# Addr.net
KiCad netlist of a schematic drawn in EAGLE
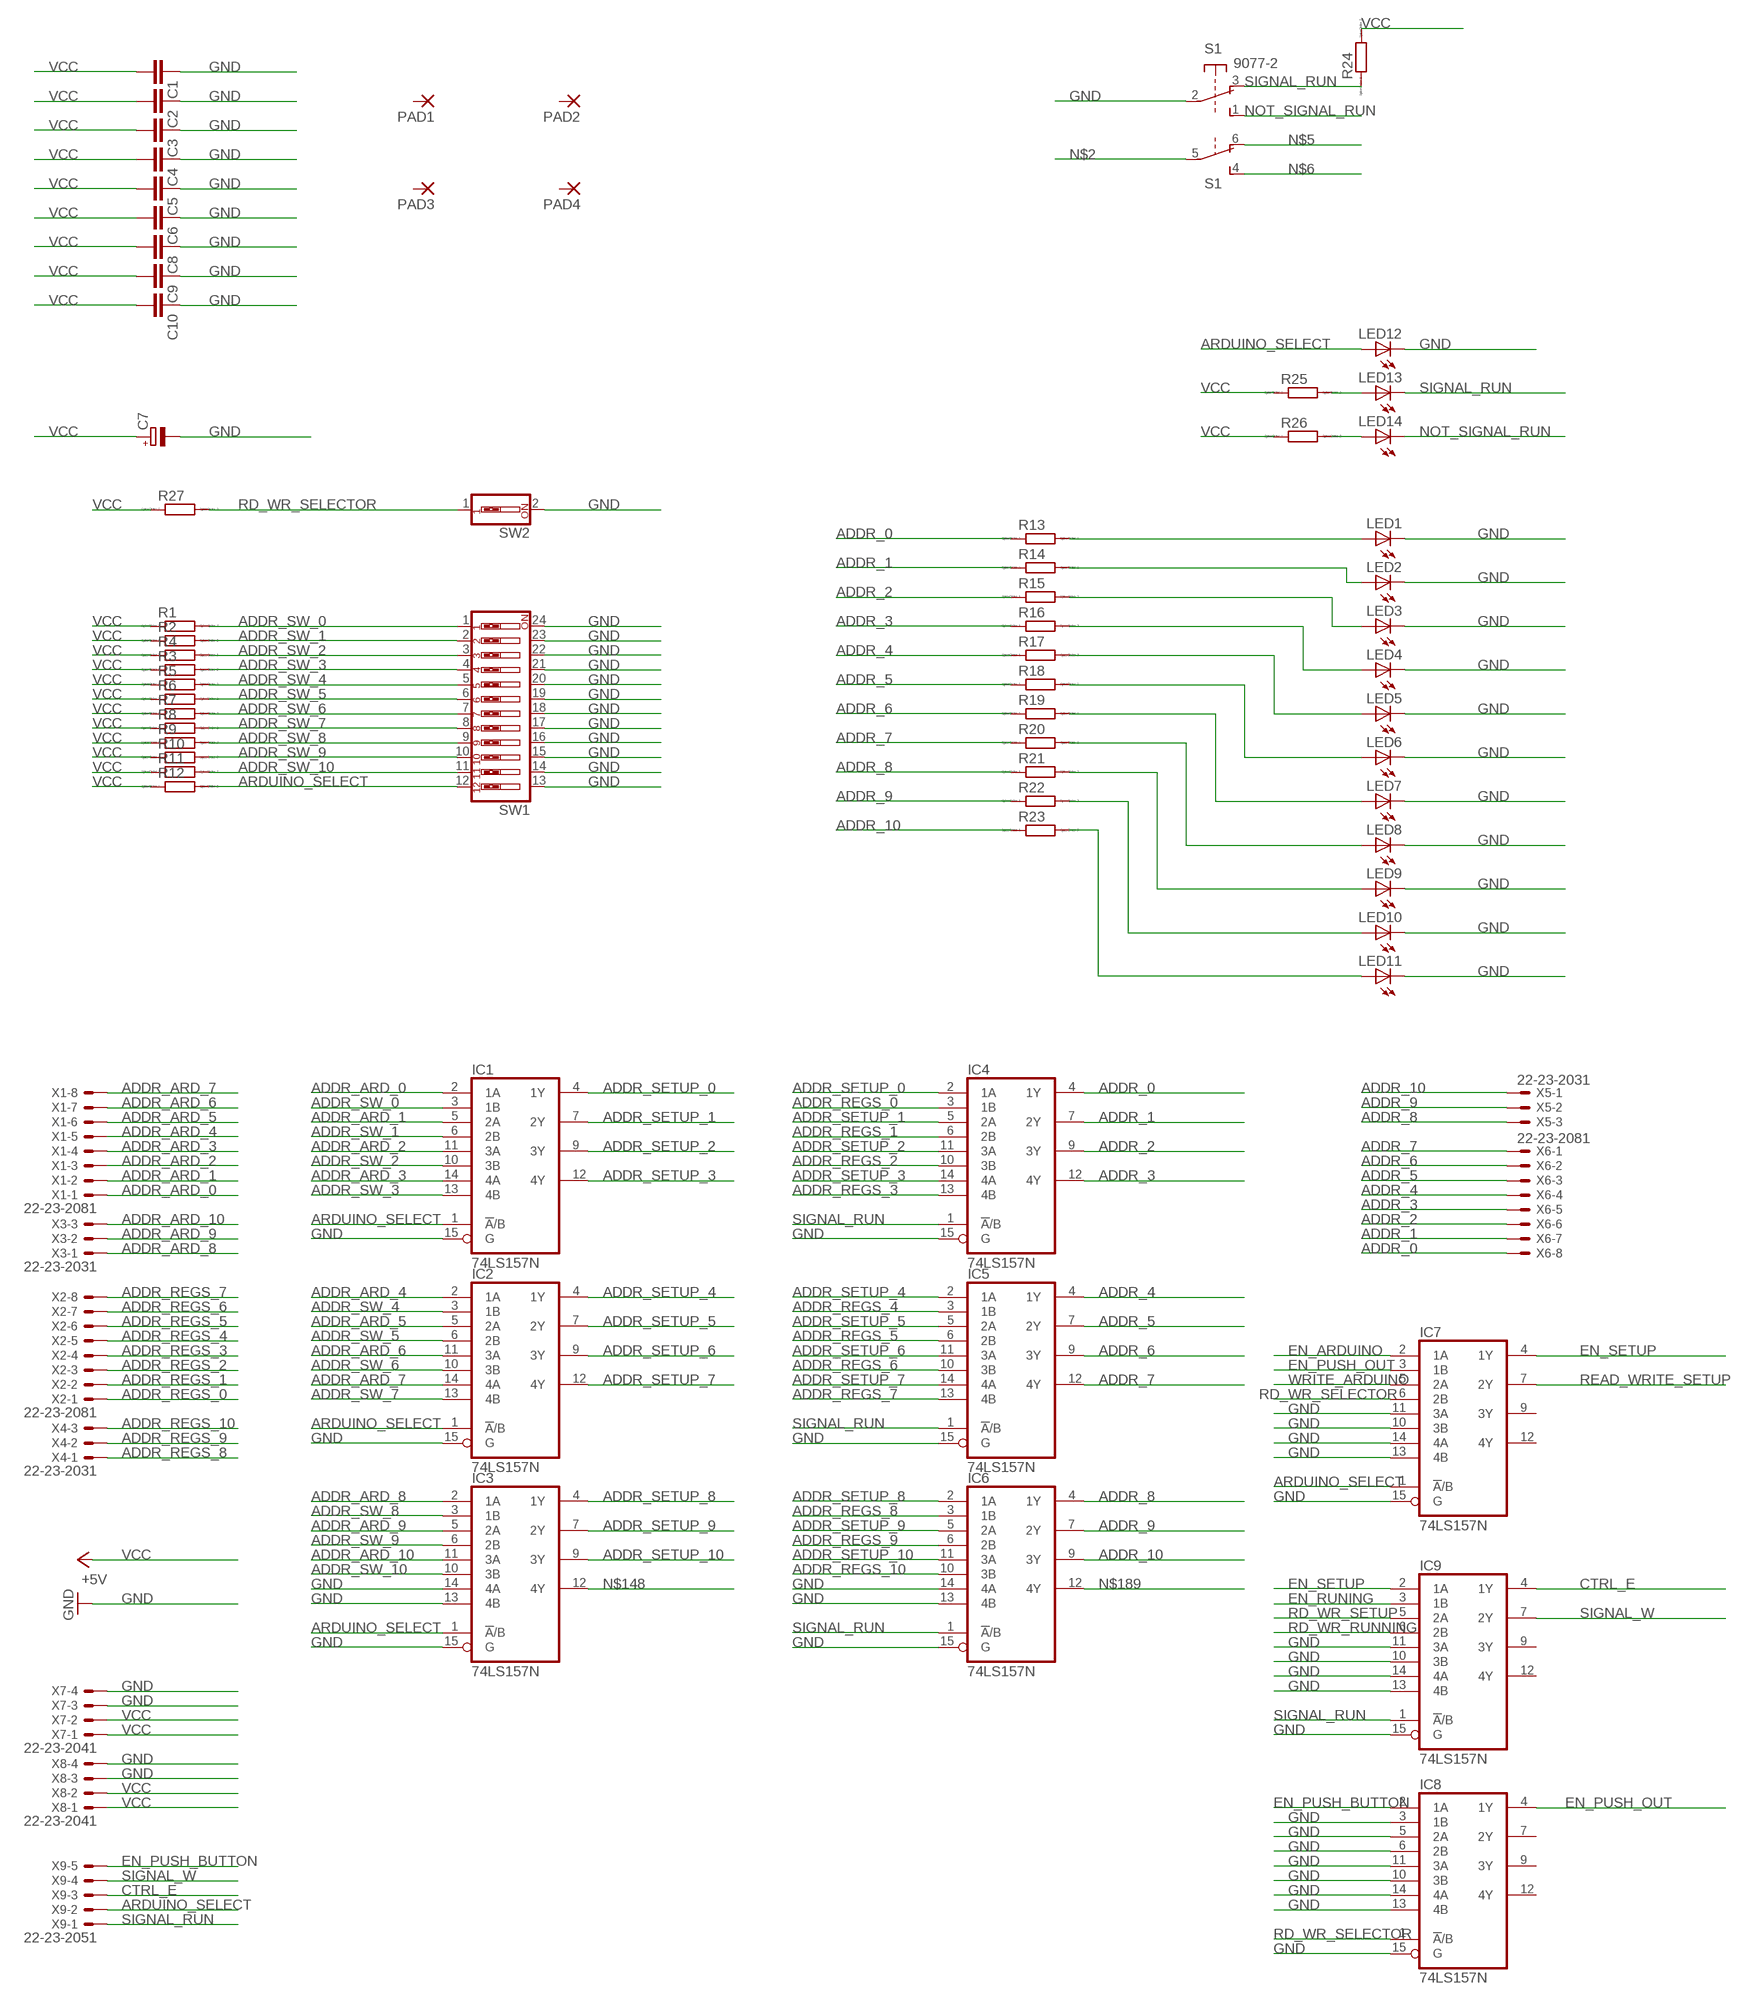
[diagram p0: schematic, sheet 1]

(export (version "E")
  (design (tool "Eeschema 10.0.6"))
  (components
    (comp (ref "C1")
      (value "C-EU025-025X050")
      (footprint "eagle-import:C025-025X050")
      (libsource (lib "eagle-import") (part "C-EU025-025X050"))
    )
    (comp (ref "C2")
      (value "C-EU025-025X050")
      (footprint "eagle-import:C025-025X050")
      (libsource (lib "eagle-import") (part "C-EU025-025X050"))
    )
    (comp (ref "C3")
      (value "C-EU025-025X050")
      (footprint "eagle-import:C025-025X050")
      (libsource (lib "eagle-import") (part "C-EU025-025X050"))
    )
    (comp (ref "C4")
      (value "C-EU025-025X050")
      (footprint "eagle-import:C025-025X050")
      (libsource (lib "eagle-import") (part "C-EU025-025X050"))
    )
    (comp (ref "C5")
      (value "C-EU025-025X050")
      (footprint "eagle-import:C025-025X050")
      (libsource (lib "eagle-import") (part "C-EU025-025X050"))
    )
    (comp (ref "C6")
      (value "C-EU025-025X050")
      (footprint "eagle-import:C025-025X050")
      (libsource (lib "eagle-import") (part "C-EU025-025X050"))
    )
    (comp (ref "C7")
      (value "CPOL-EUE2.5-6")
      (footprint "eagle-import:E2,5-6")
      (libsource (lib "eagle-import") (part "CPOL-EUE2.5-6"))
    )
    (comp (ref "C8")
      (value "C-EU025-025X050")
      (footprint "eagle-import:C025-025X050")
      (libsource (lib "eagle-import") (part "C-EU025-025X050"))
    )
    (comp (ref "C9")
      (value "C-EU025-025X050")
      (footprint "eagle-import:C025-025X050")
      (libsource (lib "eagle-import") (part "C-EU025-025X050"))
    )
    (comp (ref "C10")
      (value "C-EU025-025X050")
      (footprint "eagle-import:C025-025X050")
      (libsource (lib "eagle-import") (part "C-EU025-025X050"))
    )
    (comp (ref "IC1")
      (value "74LS157N")
      (footprint "eagle-import:DIL16")
      (libsource (lib "eagle-import") (part "74157NLS"))
    )
    (comp (ref "IC2")
      (value "74LS157N")
      (footprint "eagle-import:DIL16")
      (libsource (lib "eagle-import") (part "74157NLS"))
    )
    (comp (ref "IC3")
      (value "74LS157N")
      (footprint "eagle-import:DIL16")
      (libsource (lib "eagle-import") (part "74157NLS"))
    )
    (comp (ref "IC4")
      (value "74LS157N")
      (footprint "eagle-import:DIL16")
      (libsource (lib "eagle-import") (part "74157NLS"))
    )
    (comp (ref "IC5")
      (value "74LS157N")
      (footprint "eagle-import:DIL16")
      (libsource (lib "eagle-import") (part "74157NLS"))
    )
    (comp (ref "IC6")
      (value "74LS157N")
      (footprint "eagle-import:DIL16")
      (libsource (lib "eagle-import") (part "74157NLS"))
    )
    (comp (ref "IC7")
      (value "74LS157N")
      (footprint "eagle-import:DIL16")
      (libsource (lib "eagle-import") (part "74157NLS"))
    )
    (comp (ref "IC8")
      (value "74LS157N")
      (footprint "eagle-import:DIL16")
      (libsource (lib "eagle-import") (part "74157NLS"))
    )
    (comp (ref "IC9")
      (value "74LS157N")
      (footprint "eagle-import:DIL16")
      (libsource (lib "eagle-import") (part "74157NLS"))
    )
    (comp (ref "LED1")
      (value "LED5MM")
      (footprint "eagle-import:LED5MM")
      (libsource (lib "eagle-import") (part "LED5MM"))
    )
    (comp (ref "LED2")
      (value "LED5MM")
      (footprint "eagle-import:LED5MM")
      (libsource (lib "eagle-import") (part "LED5MM"))
    )
    (comp (ref "LED3")
      (value "LED5MM")
      (footprint "eagle-import:LED5MM")
      (libsource (lib "eagle-import") (part "LED5MM"))
    )
    (comp (ref "LED4")
      (value "LED5MM")
      (footprint "eagle-import:LED5MM")
      (libsource (lib "eagle-import") (part "LED5MM"))
    )
    (comp (ref "LED5")
      (value "LED5MM")
      (footprint "eagle-import:LED5MM")
      (libsource (lib "eagle-import") (part "LED5MM"))
    )
    (comp (ref "LED6")
      (value "LED5MM")
      (footprint "eagle-import:LED5MM")
      (libsource (lib "eagle-import") (part "LED5MM"))
    )
    (comp (ref "LED7")
      (value "LED5MM")
      (footprint "eagle-import:LED5MM")
      (libsource (lib "eagle-import") (part "LED5MM"))
    )
    (comp (ref "LED8")
      (value "LED5MM")
      (footprint "eagle-import:LED5MM")
      (libsource (lib "eagle-import") (part "LED5MM"))
    )
    (comp (ref "LED9")
      (value "LED5MM")
      (footprint "eagle-import:LED5MM")
      (libsource (lib "eagle-import") (part "LED5MM"))
    )
    (comp (ref "LED10")
      (value "LED5MM")
      (footprint "eagle-import:LED5MM")
      (libsource (lib "eagle-import") (part "LED5MM"))
    )
    (comp (ref "LED11")
      (value "LED5MM")
      (footprint "eagle-import:LED5MM")
      (libsource (lib "eagle-import") (part "LED5MM"))
    )
    (comp (ref "LED12")
      (value "LED5MM")
      (footprint "eagle-import:LED5MM")
      (libsource (lib "eagle-import") (part "LED5MM"))
    )
    (comp (ref "LED13")
      (value "LED5MM")
      (footprint "eagle-import:LED5MM")
      (libsource (lib "eagle-import") (part "LED5MM"))
    )
    (comp (ref "LED14")
      (value "LED5MM")
      (footprint "eagle-import:LED5MM")
      (libsource (lib "eagle-import") (part "LED5MM"))
    )
    (comp (ref "PAD1")
      (value "3,17/1,3")
      (footprint "eagle-import:3,17_1,3")
      (libsource (lib "eagle-import") (part "3,17/1,3"))
    )
    (comp (ref "PAD2")
      (value "3,17/1,3")
      (footprint "eagle-import:3,17_1,3")
      (libsource (lib "eagle-import") (part "3,17/1,3"))
    )
    (comp (ref "PAD3")
      (value "3,17/1,3")
      (footprint "eagle-import:3,17_1,3")
      (libsource (lib "eagle-import") (part "3,17/1,3"))
    )
    (comp (ref "PAD4")
      (value "3,17/1,3")
      (footprint "eagle-import:3,17_1,3")
      (libsource (lib "eagle-import") (part "3,17/1,3"))
    )
    (comp (ref "R1")
      (value "R0207/10")
      (footprint "eagle-import:0207_10")
      (libsource (lib "eagle-import") (part "R0207/10"))
    )
    (comp (ref "R2")
      (value "R0207/10")
      (footprint "eagle-import:0207_10")
      (libsource (lib "eagle-import") (part "R0207/10"))
    )
    (comp (ref "R3")
      (value "R0207/10")
      (footprint "eagle-import:0207_10")
      (libsource (lib "eagle-import") (part "R0207/10"))
    )
    (comp (ref "R4")
      (value "R0207/10")
      (footprint "eagle-import:0207_10")
      (libsource (lib "eagle-import") (part "R0207/10"))
    )
    (comp (ref "R5")
      (value "R0207/10")
      (footprint "eagle-import:0207_10")
      (libsource (lib "eagle-import") (part "R0207/10"))
    )
    (comp (ref "R6")
      (value "R0207/10")
      (footprint "eagle-import:0207_10")
      (libsource (lib "eagle-import") (part "R0207/10"))
    )
    (comp (ref "R7")
      (value "R0207/10")
      (footprint "eagle-import:0207_10")
      (libsource (lib "eagle-import") (part "R0207/10"))
    )
    (comp (ref "R8")
      (value "R0207/10")
      (footprint "eagle-import:0207_10")
      (libsource (lib "eagle-import") (part "R0207/10"))
    )
    (comp (ref "R9")
      (value "R0207/10")
      (footprint "eagle-import:0207_10")
      (libsource (lib "eagle-import") (part "R0207/10"))
    )
    (comp (ref "R10")
      (value "R0207/10")
      (footprint "eagle-import:0207_10")
      (libsource (lib "eagle-import") (part "R0207/10"))
    )
    (comp (ref "R11")
      (value "R0207/10")
      (footprint "eagle-import:0207_10")
      (libsource (lib "eagle-import") (part "R0207/10"))
    )
    (comp (ref "R12")
      (value "R0207/10")
      (footprint "eagle-import:0207_10")
      (libsource (lib "eagle-import") (part "R0207/10"))
    )
    (comp (ref "R13")
      (value "R0207/10")
      (footprint "eagle-import:0207_10")
      (libsource (lib "eagle-import") (part "R0207/10"))
    )
    (comp (ref "R14")
      (value "R0207/10")
      (footprint "eagle-import:0207_10")
      (libsource (lib "eagle-import") (part "R0207/10"))
    )
    (comp (ref "R15")
      (value "R0207/10")
      (footprint "eagle-import:0207_10")
      (libsource (lib "eagle-import") (part "R0207/10"))
    )
    (comp (ref "R16")
      (value "R0207/10")
      (footprint "eagle-import:0207_10")
      (libsource (lib "eagle-import") (part "R0207/10"))
    )
    (comp (ref "R17")
      (value "R0207/10")
      (footprint "eagle-import:0207_10")
      (libsource (lib "eagle-import") (part "R0207/10"))
    )
    (comp (ref "R18")
      (value "R0207/10")
      (footprint "eagle-import:0207_10")
      (libsource (lib "eagle-import") (part "R0207/10"))
    )
    (comp (ref "R19")
      (value "R0207/10")
      (footprint "eagle-import:0207_10")
      (libsource (lib "eagle-import") (part "R0207/10"))
    )
    (comp (ref "R20")
      (value "R0207/10")
      (footprint "eagle-import:0207_10")
      (libsource (lib "eagle-import") (part "R0207/10"))
    )
    (comp (ref "R21")
      (value "R0207/10")
      (footprint "eagle-import:0207_10")
      (libsource (lib "eagle-import") (part "R0207/10"))
    )
    (comp (ref "R22")
      (value "R0207/10")
      (footprint "eagle-import:0207_10")
      (libsource (lib "eagle-import") (part "R0207/10"))
    )
    (comp (ref "R23")
      (value "R0207/10")
      (footprint "eagle-import:0207_10")
      (libsource (lib "eagle-import") (part "R0207/10"))
    )
    (comp (ref "R24")
      (value "R0207/10")
      (footprint "eagle-import:0207_10")
      (libsource (lib "eagle-import") (part "R0207/10"))
    )
    (comp (ref "R25")
      (value "R0207/10")
      (footprint "eagle-import:0207_10")
      (libsource (lib "eagle-import") (part "R0207/10"))
    )
    (comp (ref "R26")
      (value "R0207/10")
      (footprint "eagle-import:0207_10")
      (libsource (lib "eagle-import") (part "R0207/10"))
    )
    (comp (ref "R27")
      (value "R0207/10")
      (footprint "eagle-import:0207_10")
      (libsource (lib "eagle-import") (part "R0207/10"))
    )
    (comp (ref "S1")
      (value "9077-2")
      (footprint "eagle-import:9077-2")
      (libsource (lib "eagle-import") (part "9077-2"))
    )
    (comp (ref "SW1")
      (value "SW_DIP-12")
      (footprint "eagle-import:EDG-12")
      (libsource (lib "eagle-import") (part "SW_DIP-12"))
    )
    (comp (ref "SW2")
      (value "SW_DIP-1")
      (footprint "eagle-import:EDG-01")
      (libsource (lib "eagle-import") (part "SW_DIP-1"))
    )
    (comp (ref "X1")
      (value "22-23-2081")
      (footprint "eagle-import:22-23-2081")
      (fields (field (name "MF") "MOLEX"))
      (libsource (lib "eagle-import") (part "22-23-2081"))
    )
    (comp (ref "X2")
      (value "22-23-2081")
      (footprint "eagle-import:22-23-2081")
      (fields (field (name "MF") "MOLEX"))
      (libsource (lib "eagle-import") (part "22-23-2081"))
    )
    (comp (ref "X3")
      (value "22-23-2031")
      (footprint "eagle-import:22-23-2031")
      (fields (field (name "MF") "MOLEX"))
      (libsource (lib "eagle-import") (part "22-23-2031"))
    )
    (comp (ref "X4")
      (value "22-23-2031")
      (footprint "eagle-import:22-23-2031")
      (fields (field (name "MF") "MOLEX"))
      (libsource (lib "eagle-import") (part "22-23-2031"))
    )
    (comp (ref "X5")
      (value "22-23-2031")
      (footprint "eagle-import:22-23-2031")
      (fields (field (name "MF") "MOLEX"))
      (libsource (lib "eagle-import") (part "22-23-2031"))
    )
    (comp (ref "X6")
      (value "22-23-2081")
      (footprint "eagle-import:22-23-2081")
      (fields (field (name "MF") "MOLEX"))
      (libsource (lib "eagle-import") (part "22-23-2081"))
    )
    (comp (ref "X7")
      (value "22-23-2041")
      (footprint "eagle-import:22-23-2041")
      (fields (field (name "MF") "MOLEX"))
      (libsource (lib "eagle-import") (part "22-23-2041"))
    )
    (comp (ref "X8")
      (value "22-23-2041")
      (footprint "eagle-import:22-23-2041")
      (fields (field (name "MF") "MOLEX"))
      (libsource (lib "eagle-import") (part "22-23-2041"))
    )
    (comp (ref "X9")
      (value "22-23-2051")
      (footprint "eagle-import:22-23-2051")
      (fields (field (name "MF") "MOLEX"))
      (libsource (lib "eagle-import") (part "22-23-2051"))
    )
  )
  (nets
    (net (code "1") (name "+5V") (class "Default")
      (node (ref "C1") (pin "2") (pinfunction "2_2") (pintype "passive"))
      (node (ref "C10") (pin "2") (pinfunction "2_2") (pintype "passive"))
      (node (ref "C2") (pin "2") (pinfunction "2_2") (pintype "passive"))
      (node (ref "C3") (pin "2") (pinfunction "2_2") (pintype "passive"))
      (node (ref "C4") (pin "2") (pinfunction "2_2") (pintype "passive"))
      (node (ref "C5") (pin "2") (pinfunction "2_2") (pintype "passive"))
      (node (ref "C6") (pin "2") (pinfunction "2_2") (pintype "passive"))
      (node (ref "C7") (pin "+") (pinfunction "+_+") (pintype "passive"))
      (node (ref "C8") (pin "2") (pinfunction "2_2") (pintype "passive"))
      (node (ref "C9") (pin "2") (pinfunction "2_2") (pintype "passive"))
      (node (ref "R1") (pin "1") (pinfunction "1_1") (pintype "passive"))
      (node (ref "R10") (pin "1") (pinfunction "1_1") (pintype "passive"))
      (node (ref "R11") (pin "1") (pinfunction "1_1") (pintype "passive"))
      (node (ref "R12") (pin "1") (pinfunction "1_1") (pintype "passive"))
      (node (ref "R2") (pin "1") (pinfunction "1_1") (pintype "passive"))
      (node (ref "R24") (pin "2") (pinfunction "2_2") (pintype "passive"))
      (node (ref "R25") (pin "1") (pinfunction "1_1") (pintype "passive"))
      (node (ref "R26") (pin "1") (pinfunction "1_1") (pintype "passive"))
      (node (ref "R27") (pin "1") (pinfunction "1_1") (pintype "passive"))
      (node (ref "R3") (pin "1") (pinfunction "1_1") (pintype "passive"))
      (node (ref "R4") (pin "1") (pinfunction "1_1") (pintype "passive"))
      (node (ref "R5") (pin "1") (pinfunction "1_1") (pintype "passive"))
      (node (ref "R6") (pin "1") (pinfunction "1_1") (pintype "passive"))
      (node (ref "R7") (pin "1") (pinfunction "1_1") (pintype "passive"))
      (node (ref "R8") (pin "1") (pinfunction "1_1") (pintype "passive"))
      (node (ref "R9") (pin "1") (pinfunction "1_1") (pintype "passive"))
      (node (ref "X7") (pin "1") (pinfunction "S_1") (pintype "passive"))
      (node (ref "X7") (pin "2") (pinfunction "S_2") (pintype "passive"))
      (node (ref "X8") (pin "1") (pinfunction "S_1") (pintype "passive"))
      (node (ref "X8") (pin "2") (pinfunction "S_2") (pintype "passive"))
    )
    (net (code "2") (name "/ADDR_0") (class "Default")
      (node (ref "IC4") (pin "4") (pinfunction "1Y_4") (pintype "output"))
      (node (ref "R13") (pin "1") (pinfunction "1_1") (pintype "passive"))
      (node (ref "X6") (pin "8") (pinfunction "S_8") (pintype "passive"))
    )
    (net (code "3") (name "/ADDR_1") (class "Default")
      (node (ref "IC4") (pin "7") (pinfunction "2Y_7") (pintype "output"))
      (node (ref "R14") (pin "1") (pinfunction "1_1") (pintype "passive"))
      (node (ref "X6") (pin "7") (pinfunction "S_7") (pintype "passive"))
    )
    (net (code "4") (name "/ADDR_2") (class "Default")
      (node (ref "IC4") (pin "9") (pinfunction "3Y_9") (pintype "output"))
      (node (ref "R15") (pin "1") (pinfunction "1_1") (pintype "passive"))
      (node (ref "X6") (pin "6") (pinfunction "S_6") (pintype "passive"))
    )
    (net (code "5") (name "/ADDR_3") (class "Default")
      (node (ref "IC4") (pin "12") (pinfunction "4Y_12") (pintype "output"))
      (node (ref "R16") (pin "1") (pinfunction "1_1") (pintype "passive"))
      (node (ref "X6") (pin "5") (pinfunction "S_5") (pintype "passive"))
    )
    (net (code "6") (name "/ADDR_4") (class "Default")
      (node (ref "IC5") (pin "4") (pinfunction "1Y_4") (pintype "output"))
      (node (ref "R17") (pin "1") (pinfunction "1_1") (pintype "passive"))
      (node (ref "X6") (pin "4") (pinfunction "S_4") (pintype "passive"))
    )
    (net (code "7") (name "/ADDR_5") (class "Default")
      (node (ref "IC5") (pin "7") (pinfunction "2Y_7") (pintype "output"))
      (node (ref "R18") (pin "1") (pinfunction "1_1") (pintype "passive"))
      (node (ref "X6") (pin "3") (pinfunction "S_3") (pintype "passive"))
    )
    (net (code "8") (name "/ADDR_6") (class "Default")
      (node (ref "IC5") (pin "9") (pinfunction "3Y_9") (pintype "output"))
      (node (ref "R19") (pin "1") (pinfunction "1_1") (pintype "passive"))
      (node (ref "X6") (pin "2") (pinfunction "S_2") (pintype "passive"))
    )
    (net (code "9") (name "/ADDR_7") (class "Default")
      (node (ref "IC5") (pin "12") (pinfunction "4Y_12") (pintype "output"))
      (node (ref "R20") (pin "1") (pinfunction "1_1") (pintype "passive"))
      (node (ref "X6") (pin "1") (pinfunction "S_1") (pintype "passive"))
    )
    (net (code "10") (name "/ADDR_8") (class "Default")
      (node (ref "IC6") (pin "4") (pinfunction "1Y_4") (pintype "output"))
      (node (ref "R21") (pin "1") (pinfunction "1_1") (pintype "passive"))
      (node (ref "X5") (pin "3") (pinfunction "S_3") (pintype "passive"))
    )
    (net (code "11") (name "/ADDR_9") (class "Default")
      (node (ref "IC6") (pin "7") (pinfunction "2Y_7") (pintype "output"))
      (node (ref "R22") (pin "1") (pinfunction "1_1") (pintype "passive"))
      (node (ref "X5") (pin "2") (pinfunction "S_2") (pintype "passive"))
    )
    (net (code "12") (name "/ADDR_10") (class "Default")
      (node (ref "IC6") (pin "9") (pinfunction "3Y_9") (pintype "output"))
      (node (ref "R23") (pin "1") (pinfunction "1_1") (pintype "passive"))
      (node (ref "X5") (pin "1") (pinfunction "S_1") (pintype "passive"))
    )
    (net (code "13") (name "/ADDR_ARD_0") (class "Default")
      (node (ref "IC1") (pin "2") (pinfunction "1A_2") (pintype "input"))
      (node (ref "X1") (pin "1") (pinfunction "S_1") (pintype "passive"))
    )
    (net (code "14") (name "/ADDR_ARD_1") (class "Default")
      (node (ref "IC1") (pin "5") (pinfunction "2A_5") (pintype "input"))
      (node (ref "X1") (pin "2") (pinfunction "S_2") (pintype "passive"))
    )
    (net (code "15") (name "/ADDR_ARD_2") (class "Default")
      (node (ref "IC1") (pin "11") (pinfunction "3A_11") (pintype "input"))
      (node (ref "X1") (pin "3") (pinfunction "S_3") (pintype "passive"))
    )
    (net (code "16") (name "/ADDR_ARD_3") (class "Default")
      (node (ref "IC1") (pin "14") (pinfunction "4A_14") (pintype "input"))
      (node (ref "X1") (pin "4") (pinfunction "S_4") (pintype "passive"))
    )
    (net (code "17") (name "/ADDR_ARD_4") (class "Default")
      (node (ref "IC2") (pin "2") (pinfunction "1A_2") (pintype "input"))
      (node (ref "X1") (pin "5") (pinfunction "S_5") (pintype "passive"))
    )
    (net (code "18") (name "/ADDR_ARD_5") (class "Default")
      (node (ref "IC2") (pin "5") (pinfunction "2A_5") (pintype "input"))
      (node (ref "X1") (pin "6") (pinfunction "S_6") (pintype "passive"))
    )
    (net (code "19") (name "/ADDR_ARD_6") (class "Default")
      (node (ref "IC2") (pin "11") (pinfunction "3A_11") (pintype "input"))
      (node (ref "X1") (pin "7") (pinfunction "S_7") (pintype "passive"))
    )
    (net (code "20") (name "/ADDR_ARD_7") (class "Default")
      (node (ref "IC2") (pin "14") (pinfunction "4A_14") (pintype "input"))
      (node (ref "X1") (pin "8") (pinfunction "S_8") (pintype "passive"))
    )
    (net (code "21") (name "/ADDR_ARD_8") (class "Default")
      (node (ref "IC3") (pin "2") (pinfunction "1A_2") (pintype "input"))
      (node (ref "X3") (pin "1") (pinfunction "S_1") (pintype "passive"))
    )
    (net (code "22") (name "/ADDR_ARD_9") (class "Default")
      (node (ref "IC3") (pin "5") (pinfunction "2A_5") (pintype "input"))
      (node (ref "X3") (pin "2") (pinfunction "S_2") (pintype "passive"))
    )
    (net (code "23") (name "/ADDR_ARD_10") (class "Default")
      (node (ref "IC3") (pin "11") (pinfunction "3A_11") (pintype "input"))
      (node (ref "X3") (pin "3") (pinfunction "S_3") (pintype "passive"))
    )
    (net (code "24") (name "/ADDR_REGS_0") (class "Default")
      (node (ref "IC4") (pin "3") (pinfunction "1B_3") (pintype "input"))
      (node (ref "X2") (pin "1") (pinfunction "S_1") (pintype "passive"))
    )
    (net (code "25") (name "/ADDR_REGS_1") (class "Default")
      (node (ref "IC4") (pin "6") (pinfunction "2B_6") (pintype "input"))
      (node (ref "X2") (pin "2") (pinfunction "S_2") (pintype "passive"))
    )
    (net (code "26") (name "/ADDR_REGS_2") (class "Default")
      (node (ref "IC4") (pin "10") (pinfunction "3B_10") (pintype "input"))
      (node (ref "X2") (pin "3") (pinfunction "S_3") (pintype "passive"))
    )
    (net (code "27") (name "/ADDR_REGS_3") (class "Default")
      (node (ref "IC4") (pin "13") (pinfunction "4B_13") (pintype "input"))
      (node (ref "X2") (pin "4") (pinfunction "S_4") (pintype "passive"))
    )
    (net (code "28") (name "/ADDR_REGS_4") (class "Default")
      (node (ref "IC5") (pin "3") (pinfunction "1B_3") (pintype "input"))
      (node (ref "X2") (pin "5") (pinfunction "S_5") (pintype "passive"))
    )
    (net (code "29") (name "/ADDR_REGS_5") (class "Default")
      (node (ref "IC5") (pin "6") (pinfunction "2B_6") (pintype "input"))
      (node (ref "X2") (pin "6") (pinfunction "S_6") (pintype "passive"))
    )
    (net (code "30") (name "/ADDR_REGS_6") (class "Default")
      (node (ref "IC5") (pin "10") (pinfunction "3B_10") (pintype "input"))
      (node (ref "X2") (pin "7") (pinfunction "S_7") (pintype "passive"))
    )
    (net (code "31") (name "/ADDR_REGS_7") (class "Default")
      (node (ref "IC5") (pin "13") (pinfunction "4B_13") (pintype "input"))
      (node (ref "X2") (pin "8") (pinfunction "S_8") (pintype "passive"))
    )
    (net (code "32") (name "/ADDR_REGS_8") (class "Default")
      (node (ref "IC6") (pin "3") (pinfunction "1B_3") (pintype "input"))
      (node (ref "X4") (pin "1") (pinfunction "S_1") (pintype "passive"))
    )
    (net (code "33") (name "/ADDR_REGS_9") (class "Default")
      (node (ref "IC6") (pin "6") (pinfunction "2B_6") (pintype "input"))
      (node (ref "X4") (pin "2") (pinfunction "S_2") (pintype "passive"))
    )
    (net (code "34") (name "/ADDR_REGS_10") (class "Default")
      (node (ref "IC6") (pin "10") (pinfunction "3B_10") (pintype "input"))
      (node (ref "X4") (pin "3") (pinfunction "S_3") (pintype "passive"))
    )
    (net (code "35") (name "/ADDR_SETUP_0") (class "Default")
      (node (ref "IC1") (pin "4") (pinfunction "1Y_4") (pintype "output"))
      (node (ref "IC4") (pin "2") (pinfunction "1A_2") (pintype "input"))
    )
    (net (code "36") (name "/ADDR_SETUP_1") (class "Default")
      (node (ref "IC1") (pin "7") (pinfunction "2Y_7") (pintype "output"))
      (node (ref "IC4") (pin "5") (pinfunction "2A_5") (pintype "input"))
    )
    (net (code "37") (name "/ADDR_SETUP_2") (class "Default")
      (node (ref "IC1") (pin "9") (pinfunction "3Y_9") (pintype "output"))
      (node (ref "IC4") (pin "11") (pinfunction "3A_11") (pintype "input"))
    )
    (net (code "38") (name "/ADDR_SETUP_3") (class "Default")
      (node (ref "IC1") (pin "12") (pinfunction "4Y_12") (pintype "output"))
      (node (ref "IC4") (pin "14") (pinfunction "4A_14") (pintype "input"))
    )
    (net (code "39") (name "/ADDR_SETUP_4") (class "Default")
      (node (ref "IC2") (pin "4") (pinfunction "1Y_4") (pintype "output"))
      (node (ref "IC5") (pin "2") (pinfunction "1A_2") (pintype "input"))
    )
    (net (code "40") (name "/ADDR_SETUP_5") (class "Default")
      (node (ref "IC2") (pin "7") (pinfunction "2Y_7") (pintype "output"))
      (node (ref "IC5") (pin "5") (pinfunction "2A_5") (pintype "input"))
    )
    (net (code "41") (name "/ADDR_SETUP_6") (class "Default")
      (node (ref "IC2") (pin "9") (pinfunction "3Y_9") (pintype "output"))
      (node (ref "IC5") (pin "11") (pinfunction "3A_11") (pintype "input"))
    )
    (net (code "42") (name "/ADDR_SETUP_7") (class "Default")
      (node (ref "IC2") (pin "12") (pinfunction "4Y_12") (pintype "output"))
      (node (ref "IC5") (pin "14") (pinfunction "4A_14") (pintype "input"))
    )
    (net (code "43") (name "/ADDR_SETUP_8") (class "Default")
      (node (ref "IC3") (pin "4") (pinfunction "1Y_4") (pintype "output"))
      (node (ref "IC6") (pin "2") (pinfunction "1A_2") (pintype "input"))
    )
    (net (code "44") (name "/ADDR_SETUP_9") (class "Default")
      (node (ref "IC3") (pin "7") (pinfunction "2Y_7") (pintype "output"))
      (node (ref "IC6") (pin "5") (pinfunction "2A_5") (pintype "input"))
    )
    (net (code "45") (name "/ADDR_SETUP_10") (class "Default")
      (node (ref "IC3") (pin "9") (pinfunction "3Y_9") (pintype "output"))
      (node (ref "IC6") (pin "11") (pinfunction "3A_11") (pintype "input"))
    )
    (net (code "46") (name "/ADDR_SW_0") (class "Default")
      (node (ref "IC1") (pin "3") (pinfunction "1B_3") (pintype "input"))
      (node (ref "R1") (pin "2") (pinfunction "2_2") (pintype "passive"))
      (node (ref "SW1") (pin "1") (pinfunction "1_1") (pintype "passive"))
    )
    (net (code "47") (name "/ADDR_SW_1") (class "Default")
      (node (ref "IC1") (pin "6") (pinfunction "2B_6") (pintype "input"))
      (node (ref "R2") (pin "2") (pinfunction "2_2") (pintype "passive"))
      (node (ref "SW1") (pin "2") (pinfunction "2_2") (pintype "passive"))
    )
    (net (code "48") (name "/ADDR_SW_2") (class "Default")
      (node (ref "IC1") (pin "10") (pinfunction "3B_10") (pintype "input"))
      (node (ref "R4") (pin "2") (pinfunction "2_2") (pintype "passive"))
      (node (ref "SW1") (pin "3") (pinfunction "3_3") (pintype "passive"))
    )
    (net (code "49") (name "/ADDR_SW_3") (class "Default")
      (node (ref "IC1") (pin "13") (pinfunction "4B_13") (pintype "input"))
      (node (ref "R3") (pin "2") (pinfunction "2_2") (pintype "passive"))
      (node (ref "SW1") (pin "4") (pinfunction "4_4") (pintype "passive"))
    )
    (net (code "50") (name "/ADDR_SW_4") (class "Default")
      (node (ref "IC2") (pin "3") (pinfunction "1B_3") (pintype "input"))
      (node (ref "R5") (pin "2") (pinfunction "2_2") (pintype "passive"))
      (node (ref "SW1") (pin "5") (pinfunction "5_5") (pintype "passive"))
    )
    (net (code "51") (name "/ADDR_SW_5") (class "Default")
      (node (ref "IC2") (pin "6") (pinfunction "2B_6") (pintype "input"))
      (node (ref "R6") (pin "2") (pinfunction "2_2") (pintype "passive"))
      (node (ref "SW1") (pin "6") (pinfunction "6_6") (pintype "passive"))
    )
    (net (code "52") (name "/ADDR_SW_6") (class "Default")
      (node (ref "IC2") (pin "10") (pinfunction "3B_10") (pintype "input"))
      (node (ref "R7") (pin "2") (pinfunction "2_2") (pintype "passive"))
      (node (ref "SW1") (pin "7") (pinfunction "7_7") (pintype "passive"))
    )
    (net (code "53") (name "/ADDR_SW_7") (class "Default")
      (node (ref "IC2") (pin "13") (pinfunction "4B_13") (pintype "input"))
      (node (ref "R8") (pin "2") (pinfunction "2_2") (pintype "passive"))
      (node (ref "SW1") (pin "8") (pinfunction "8_8") (pintype "passive"))
    )
    (net (code "54") (name "/ADDR_SW_8") (class "Default")
      (node (ref "IC3") (pin "3") (pinfunction "1B_3") (pintype "input"))
      (node (ref "R9") (pin "2") (pinfunction "2_2") (pintype "passive"))
      (node (ref "SW1") (pin "9") (pinfunction "9_9") (pintype "passive"))
    )
    (net (code "55") (name "/ADDR_SW_9") (class "Default")
      (node (ref "IC3") (pin "6") (pinfunction "2B_6") (pintype "input"))
      (node (ref "R10") (pin "2") (pinfunction "2_2") (pintype "passive"))
      (node (ref "SW1") (pin "10") (pinfunction "10_10") (pintype "passive"))
    )
    (net (code "56") (name "/ADDR_SW_10") (class "Default")
      (node (ref "IC3") (pin "10") (pinfunction "3B_10") (pintype "input"))
      (node (ref "R11") (pin "2") (pinfunction "2_2") (pintype "passive"))
      (node (ref "SW1") (pin "11") (pinfunction "11_11") (pintype "passive"))
    )
    (net (code "57") (name "/ARDUINO_SELECT") (class "Default")
      (node (ref "IC1") (pin "1") (pinfunction "~{A}/B_1") (pintype "input"))
      (node (ref "IC2") (pin "1") (pinfunction "~{A}/B_1") (pintype "input"))
      (node (ref "IC3") (pin "1") (pinfunction "~{A}/B_1") (pintype "input"))
      (node (ref "IC7") (pin "1") (pinfunction "~{A}/B_1") (pintype "input"))
      (node (ref "LED12") (pin "A") (pinfunction "A_A") (pintype "passive"))
      (node (ref "R12") (pin "2") (pinfunction "2_2") (pintype "passive"))
      (node (ref "SW1") (pin "12") (pinfunction "12_12") (pintype "passive"))
      (node (ref "X9") (pin "2") (pinfunction "S_2") (pintype "passive"))
    )
    (net (code "58") (name "/CTRL_E") (class "Default")
      (node (ref "IC9") (pin "4") (pinfunction "1Y_4") (pintype "output"))
      (node (ref "X9") (pin "3") (pinfunction "S_3") (pintype "passive"))
    )
    (net (code "59") (name "/EN_ARDUINO") (class "Default")
      (node (ref "IC7") (pin "2") (pinfunction "1A_2") (pintype "input"))
    )
    (net (code "60") (name "/EN_PUSH_BUTTON") (class "Default")
      (node (ref "IC8") (pin "2") (pinfunction "1A_2") (pintype "input"))
      (node (ref "X9") (pin "5") (pinfunction "S_5") (pintype "passive"))
    )
    (net (code "61") (name "/EN_PUSH_OUT") (class "Default")
      (node (ref "IC7") (pin "3") (pinfunction "1B_3") (pintype "input"))
      (node (ref "IC8") (pin "4") (pinfunction "1Y_4") (pintype "output"))
    )
    (net (code "62") (name "/EN_RUNING") (class "Default")
      (node (ref "IC9") (pin "3") (pinfunction "1B_3") (pintype "input"))
    )
    (net (code "63") (name "/EN_SETUP") (class "Default")
      (node (ref "IC7") (pin "4") (pinfunction "1Y_4") (pintype "output"))
      (node (ref "IC9") (pin "2") (pinfunction "1A_2") (pintype "input"))
    )
    (net (code "64") (name "/N$2") (class "Default")
      (node (ref "S1") (pin "5") (pinfunction "P_5") (pintype "passive"))
    )
    (net (code "65") (name "/N$5") (class "Default")
      (node (ref "S1") (pin "6") (pinfunction "O_6") (pintype "passive"))
    )
    (net (code "66") (name "/N$6") (class "Default")
      (node (ref "S1") (pin "4") (pinfunction "S_4") (pintype "passive"))
    )
    (net (code "67") (name "/N$148") (class "Default")
      (node (ref "IC3") (pin "12") (pinfunction "4Y_12") (pintype "output"))
    )
    (net (code "68") (name "/N$189") (class "Default")
      (node (ref "IC6") (pin "12") (pinfunction "4Y_12") (pintype "output"))
    )
    (net (code "69") (name "/NOT_SIGNAL_RUN") (class "Default")
      (node (ref "LED14") (pin "K") (pinfunction "C_K") (pintype "passive"))
      (node (ref "S1") (pin "1") (pinfunction "S_1") (pintype "passive"))
    )
    (net (code "70") (name "/RD_WR_RUNNING") (class "Default")
      (node (ref "IC9") (pin "6") (pinfunction "2B_6") (pintype "input"))
    )
    (net (code "71") (name "/RD_WR_SELECTOR") (class "Default")
      (node (ref "IC7") (pin "6") (pinfunction "2B_6") (pintype "input"))
      (node (ref "IC8") (pin "1") (pinfunction "~{A}/B_1") (pintype "input"))
      (node (ref "R27") (pin "2") (pinfunction "2_2") (pintype "passive"))
      (node (ref "SW2") (pin "1") (pinfunction "1_1") (pintype "passive"))
    )
    (net (code "72") (name "/RD_WR_SETUP") (class "Default")
      (node (ref "IC9") (pin "5") (pinfunction "2A_5") (pintype "input"))
    )
    (net (code "73") (name "/READ_WRITE_SETUP") (class "Default")
      (node (ref "IC7") (pin "7") (pinfunction "2Y_7") (pintype "output"))
    )
    (net (code "74") (name "/SIGNAL_RUN") (class "Default")
      (node (ref "IC4") (pin "1") (pinfunction "~{A}/B_1") (pintype "input"))
      (node (ref "IC5") (pin "1") (pinfunction "~{A}/B_1") (pintype "input"))
      (node (ref "IC6") (pin "1") (pinfunction "~{A}/B_1") (pintype "input"))
      (node (ref "IC9") (pin "1") (pinfunction "~{A}/B_1") (pintype "input"))
      (node (ref "LED13") (pin "K") (pinfunction "C_K") (pintype "passive"))
      (node (ref "R24") (pin "1") (pinfunction "1_1") (pintype "passive"))
      (node (ref "S1") (pin "3") (pinfunction "O_3") (pintype "passive"))
      (node (ref "X9") (pin "1") (pinfunction "S_1") (pintype "passive"))
    )
    (net (code "75") (name "/SIGNAL_W") (class "Default")
      (node (ref "IC9") (pin "7") (pinfunction "2Y_7") (pintype "output"))
      (node (ref "X9") (pin "4") (pinfunction "S_4") (pintype "passive"))
    )
    (net (code "76") (name "/WRITE_ARDUINO") (class "Default")
      (node (ref "IC7") (pin "5") (pinfunction "2A_5") (pintype "input"))
    )
    (net (code "77") (name "GND") (class "Default")
      (node (ref "C1") (pin "1") (pinfunction "1_1") (pintype "passive"))
      (node (ref "C10") (pin "1") (pinfunction "1_1") (pintype "passive"))
      (node (ref "C2") (pin "1") (pinfunction "1_1") (pintype "passive"))
      (node (ref "C3") (pin "1") (pinfunction "1_1") (pintype "passive"))
      (node (ref "C4") (pin "1") (pinfunction "1_1") (pintype "passive"))
      (node (ref "C5") (pin "1") (pinfunction "1_1") (pintype "passive"))
      (node (ref "C6") (pin "1") (pinfunction "1_1") (pintype "passive"))
      (node (ref "C7") (pin "-") (pinfunction "-_-") (pintype "passive"))
      (node (ref "C8") (pin "1") (pinfunction "1_1") (pintype "passive"))
      (node (ref "C9") (pin "1") (pinfunction "1_1") (pintype "passive"))
      (node (ref "IC1") (pin "15") (pinfunction "G_15") (pintype "input"))
      (node (ref "IC2") (pin "15") (pinfunction "G_15") (pintype "input"))
      (node (ref "IC3") (pin "13") (pinfunction "4B_13") (pintype "input"))
      (node (ref "IC3") (pin "14") (pinfunction "4A_14") (pintype "input"))
      (node (ref "IC3") (pin "15") (pinfunction "G_15") (pintype "input"))
      (node (ref "IC4") (pin "15") (pinfunction "G_15") (pintype "input"))
      (node (ref "IC5") (pin "15") (pinfunction "G_15") (pintype "input"))
      (node (ref "IC6") (pin "13") (pinfunction "4B_13") (pintype "input"))
      (node (ref "IC6") (pin "14") (pinfunction "4A_14") (pintype "input"))
      (node (ref "IC6") (pin "15") (pinfunction "G_15") (pintype "input"))
      (node (ref "IC7") (pin "10") (pinfunction "3B_10") (pintype "input"))
      (node (ref "IC7") (pin "11") (pinfunction "3A_11") (pintype "input"))
      (node (ref "IC7") (pin "13") (pinfunction "4B_13") (pintype "input"))
      (node (ref "IC7") (pin "14") (pinfunction "4A_14") (pintype "input"))
      (node (ref "IC7") (pin "15") (pinfunction "G_15") (pintype "input"))
      (node (ref "IC8") (pin "10") (pinfunction "3B_10") (pintype "input"))
      (node (ref "IC8") (pin "11") (pinfunction "3A_11") (pintype "input"))
      (node (ref "IC8") (pin "13") (pinfunction "4B_13") (pintype "input"))
      (node (ref "IC8") (pin "14") (pinfunction "4A_14") (pintype "input"))
      (node (ref "IC8") (pin "15") (pinfunction "G_15") (pintype "input"))
      (node (ref "IC8") (pin "3") (pinfunction "1B_3") (pintype "input"))
      (node (ref "IC8") (pin "5") (pinfunction "2A_5") (pintype "input"))
      (node (ref "IC8") (pin "6") (pinfunction "2B_6") (pintype "input"))
      (node (ref "IC9") (pin "10") (pinfunction "3B_10") (pintype "input"))
      (node (ref "IC9") (pin "11") (pinfunction "3A_11") (pintype "input"))
      (node (ref "IC9") (pin "13") (pinfunction "4B_13") (pintype "input"))
      (node (ref "IC9") (pin "14") (pinfunction "4A_14") (pintype "input"))
      (node (ref "IC9") (pin "15") (pinfunction "G_15") (pintype "input"))
      (node (ref "LED1") (pin "K") (pinfunction "C_K") (pintype "passive"))
      (node (ref "LED10") (pin "K") (pinfunction "C_K") (pintype "passive"))
      (node (ref "LED11") (pin "K") (pinfunction "C_K") (pintype "passive"))
      (node (ref "LED12") (pin "K") (pinfunction "C_K") (pintype "passive"))
      (node (ref "LED2") (pin "K") (pinfunction "C_K") (pintype "passive"))
      (node (ref "LED3") (pin "K") (pinfunction "C_K") (pintype "passive"))
      (node (ref "LED4") (pin "K") (pinfunction "C_K") (pintype "passive"))
      (node (ref "LED5") (pin "K") (pinfunction "C_K") (pintype "passive"))
      (node (ref "LED6") (pin "K") (pinfunction "C_K") (pintype "passive"))
      (node (ref "LED7") (pin "K") (pinfunction "C_K") (pintype "passive"))
      (node (ref "LED8") (pin "K") (pinfunction "C_K") (pintype "passive"))
      (node (ref "LED9") (pin "K") (pinfunction "C_K") (pintype "passive"))
      (node (ref "S1") (pin "2") (pinfunction "P_2") (pintype "passive"))
      (node (ref "SW1") (pin "13") (pinfunction "13_13") (pintype "passive"))
      (node (ref "SW1") (pin "14") (pinfunction "14_14") (pintype "passive"))
      (node (ref "SW1") (pin "15") (pinfunction "15_15") (pintype "passive"))
      (node (ref "SW1") (pin "16") (pinfunction "16_16") (pintype "passive"))
      (node (ref "SW1") (pin "17") (pinfunction "17_17") (pintype "passive"))
      (node (ref "SW1") (pin "18") (pinfunction "18_18") (pintype "passive"))
      (node (ref "SW1") (pin "19") (pinfunction "19_19") (pintype "passive"))
      (node (ref "SW1") (pin "20") (pinfunction "20_20") (pintype "passive"))
      (node (ref "SW1") (pin "21") (pinfunction "21_21") (pintype "passive"))
      (node (ref "SW1") (pin "22") (pinfunction "22_22") (pintype "passive"))
      (node (ref "SW1") (pin "23") (pinfunction "23_23") (pintype "passive"))
      (node (ref "SW1") (pin "24") (pinfunction "24_24") (pintype "passive"))
      (node (ref "SW2") (pin "2") (pinfunction "2_2") (pintype "passive"))
      (node (ref "X7") (pin "3") (pinfunction "S_3") (pintype "passive"))
      (node (ref "X7") (pin "4") (pinfunction "S_4") (pintype "passive"))
      (node (ref "X8") (pin "3") (pinfunction "S_3") (pintype "passive"))
      (node (ref "X8") (pin "4") (pinfunction "S_4") (pintype "passive"))
    )
    (net (code "78") (name "Net-(LED1-PadA)") (class "Default")
      (node (ref "LED1") (pin "A") (pinfunction "A_A") (pintype "passive"))
      (node (ref "R13") (pin "2") (pinfunction "2_2") (pintype "passive"))
    )
    (net (code "79") (name "Net-(LED2-PadA)") (class "Default")
      (node (ref "LED2") (pin "A") (pinfunction "A_A") (pintype "passive"))
      (node (ref "R14") (pin "2") (pinfunction "2_2") (pintype "passive"))
    )
    (net (code "80") (name "Net-(LED3-PadA)") (class "Default")
      (node (ref "LED3") (pin "A") (pinfunction "A_A") (pintype "passive"))
      (node (ref "R15") (pin "2") (pinfunction "2_2") (pintype "passive"))
    )
    (net (code "81") (name "Net-(LED4-PadA)") (class "Default")
      (node (ref "LED4") (pin "A") (pinfunction "A_A") (pintype "passive"))
      (node (ref "R16") (pin "2") (pinfunction "2_2") (pintype "passive"))
    )
    (net (code "82") (name "Net-(LED5-PadA)") (class "Default")
      (node (ref "LED5") (pin "A") (pinfunction "A_A") (pintype "passive"))
      (node (ref "R17") (pin "2") (pinfunction "2_2") (pintype "passive"))
    )
    (net (code "83") (name "Net-(LED6-PadA)") (class "Default")
      (node (ref "LED6") (pin "A") (pinfunction "A_A") (pintype "passive"))
      (node (ref "R18") (pin "2") (pinfunction "2_2") (pintype "passive"))
    )
    (net (code "84") (name "Net-(LED7-PadA)") (class "Default")
      (node (ref "LED7") (pin "A") (pinfunction "A_A") (pintype "passive"))
      (node (ref "R19") (pin "2") (pinfunction "2_2") (pintype "passive"))
    )
    (net (code "85") (name "Net-(LED8-PadA)") (class "Default")
      (node (ref "LED8") (pin "A") (pinfunction "A_A") (pintype "passive"))
      (node (ref "R20") (pin "2") (pinfunction "2_2") (pintype "passive"))
    )
    (net (code "86") (name "Net-(LED9-PadA)") (class "Default")
      (node (ref "LED9") (pin "A") (pinfunction "A_A") (pintype "passive"))
      (node (ref "R21") (pin "2") (pinfunction "2_2") (pintype "passive"))
    )
    (net (code "87") (name "Net-(LED10-PadA)") (class "Default")
      (node (ref "LED10") (pin "A") (pinfunction "A_A") (pintype "passive"))
      (node (ref "R22") (pin "2") (pinfunction "2_2") (pintype "passive"))
    )
    (net (code "88") (name "Net-(LED11-PadA)") (class "Default")
      (node (ref "LED11") (pin "A") (pinfunction "A_A") (pintype "passive"))
      (node (ref "R23") (pin "2") (pinfunction "2_2") (pintype "passive"))
    )
    (net (code "89") (name "Net-(LED13-PadA)") (class "Default")
      (node (ref "LED13") (pin "A") (pinfunction "A_A") (pintype "passive"))
      (node (ref "R25") (pin "2") (pinfunction "2_2") (pintype "passive"))
    )
    (net (code "90") (name "Net-(LED14-PadA)") (class "Default")
      (node (ref "LED14") (pin "A") (pinfunction "A_A") (pintype "passive"))
      (node (ref "R26") (pin "2") (pinfunction "2_2") (pintype "passive"))
    )
    (net (code "91") (name "unconnected-(IC7A-3Y-Pad9)") (class "Default")
      (node (ref "IC7") (pin "9") (pinfunction "3Y_9") (pintype "output"))
    )
    (net (code "92") (name "unconnected-(IC7A-4Y-Pad12)") (class "Default")
      (node (ref "IC7") (pin "12") (pinfunction "4Y_12") (pintype "output"))
    )
    (net (code "93") (name "unconnected-(IC8A-2Y-Pad7)") (class "Default")
      (node (ref "IC8") (pin "7") (pinfunction "2Y_7") (pintype "output"))
    )
    (net (code "94") (name "unconnected-(IC8A-3Y-Pad9)") (class "Default")
      (node (ref "IC8") (pin "9") (pinfunction "3Y_9") (pintype "output"))
    )
    (net (code "95") (name "unconnected-(IC8A-4Y-Pad12)") (class "Default")
      (node (ref "IC8") (pin "12") (pinfunction "4Y_12") (pintype "output"))
    )
    (net (code "96") (name "unconnected-(IC9A-3Y-Pad9)") (class "Default")
      (node (ref "IC9") (pin "9") (pinfunction "3Y_9") (pintype "output"))
    )
    (net (code "97") (name "unconnected-(IC9A-4Y-Pad12)") (class "Default")
      (node (ref "IC9") (pin "12") (pinfunction "4Y_12") (pintype "output"))
    )
    (net (code "98") (name "unconnected-(PAD1-P-Pad1)") (class "Default")
      (node (ref "PAD1") (pin "1") (pinfunction "P_1") (pintype "passive"))
    )
    (net (code "99") (name "unconnected-(PAD2-P-Pad1)") (class "Default")
      (node (ref "PAD2") (pin "1") (pinfunction "P_1") (pintype "passive"))
    )
    (net (code "100") (name "unconnected-(PAD3-P-Pad1)") (class "Default")
      (node (ref "PAD3") (pin "1") (pinfunction "P_1") (pintype "passive"))
    )
    (net (code "101") (name "unconnected-(PAD4-P-Pad1)") (class "Default")
      (node (ref "PAD4") (pin "1") (pinfunction "P_1") (pintype "passive"))
    )
  )
)
